# led_matrix_serial.net
KiCad netlist of a schematic drawn in Altium Designer
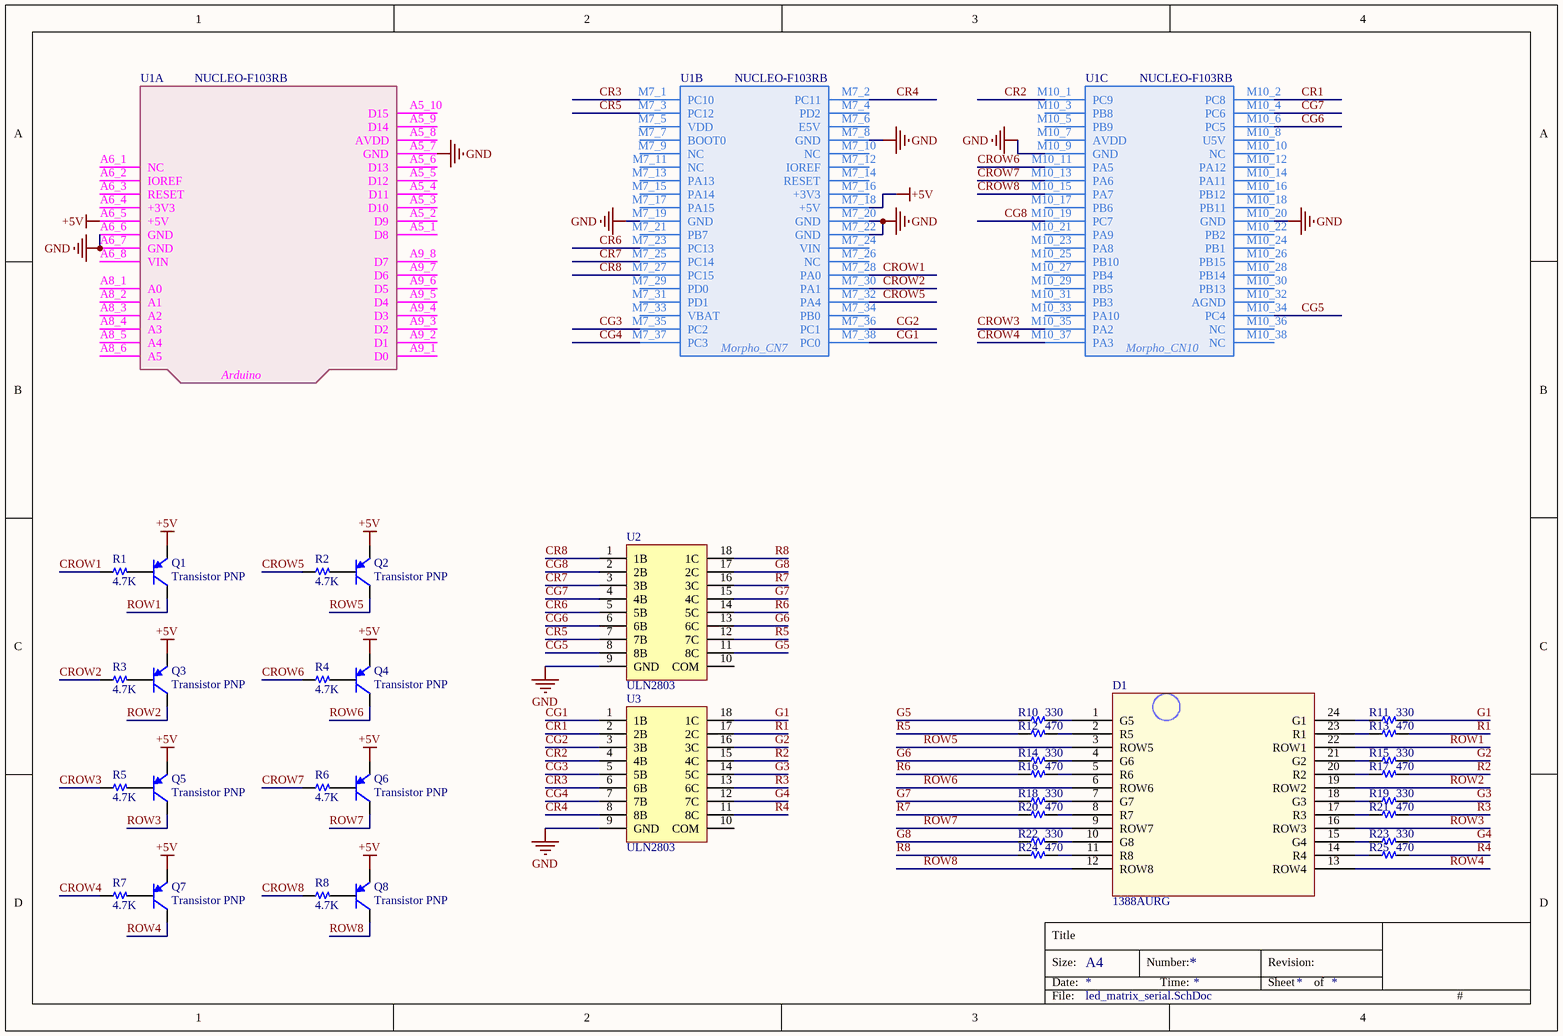
[diagram p0: led_matrix_serial.SchDoc]

(export (version "E")
  (design (tool "Eeschema 10.0.6"))
  (components
    (comp (ref "D1")
      (value "1388AURG")
      (footprint "LED/MATRIX/1388")
      (description "1388AURG, Common-Anode, LED Matrix 8x8, RED-GREEN, 32x32mm")
      (libsource (lib "chipfc_altium_libs") (part "LED MATRIX 1388AURG"))
    )
    (comp (ref "Q1")
      (value "Transistor PNP")
      (footprint "SOT-23")
      (description "PNP Bipolar Transistor")
      (libsource (lib "chipfc_altium_libs") (part "Transistor PNP"))
    )
    (comp (ref "Q2")
      (value "Transistor PNP")
      (footprint "SOT-23")
      (description "PNP Bipolar Transistor")
      (libsource (lib "chipfc_altium_libs") (part "Transistor PNP"))
    )
    (comp (ref "Q3")
      (value "Transistor PNP")
      (footprint "SOT-23")
      (description "PNP Bipolar Transistor")
      (libsource (lib "chipfc_altium_libs") (part "Transistor PNP"))
    )
    (comp (ref "Q4")
      (value "Transistor PNP")
      (footprint "SOT-23")
      (description "PNP Bipolar Transistor")
      (libsource (lib "chipfc_altium_libs") (part "Transistor PNP"))
    )
    (comp (ref "Q5")
      (value "Transistor PNP")
      (footprint "SOT-23")
      (description "PNP Bipolar Transistor")
      (libsource (lib "chipfc_altium_libs") (part "Transistor PNP"))
    )
    (comp (ref "Q6")
      (value "Transistor PNP")
      (footprint "SOT-23")
      (description "PNP Bipolar Transistor")
      (libsource (lib "chipfc_altium_libs") (part "Transistor PNP"))
    )
    (comp (ref "Q7")
      (value "Transistor PNP")
      (footprint "SOT-23")
      (description "PNP Bipolar Transistor")
      (libsource (lib "chipfc_altium_libs") (part "Transistor PNP"))
    )
    (comp (ref "Q8")
      (value "Transistor PNP")
      (footprint "SOT-23")
      (description "PNP Bipolar Transistor")
      (libsource (lib "chipfc_altium_libs") (part "Transistor PNP"))
    )
    (comp (ref "R1")
      (value "4.7K")
      (footprint "R 0805")
      (description "Resistor")
      (libsource (lib "chipfc_altium_libs") (part "Resistor"))
    )
    (comp (ref "R2")
      (value "4.7K")
      (footprint "R 0805")
      (description "Resistor")
      (libsource (lib "chipfc_altium_libs") (part "Resistor"))
    )
    (comp (ref "R3")
      (value "4.7K")
      (footprint "R 0805")
      (description "Resistor")
      (libsource (lib "chipfc_altium_libs") (part "Resistor"))
    )
    (comp (ref "R4")
      (value "4.7K")
      (footprint "R 0805")
      (description "Resistor")
      (libsource (lib "chipfc_altium_libs") (part "Resistor"))
    )
    (comp (ref "R5")
      (value "4.7K")
      (footprint "R 0805")
      (description "Resistor")
      (libsource (lib "chipfc_altium_libs") (part "Resistor"))
    )
    (comp (ref "R6")
      (value "4.7K")
      (footprint "R 0805")
      (description "Resistor")
      (libsource (lib "chipfc_altium_libs") (part "Resistor"))
    )
    (comp (ref "R7")
      (value "4.7K")
      (footprint "R 0805")
      (description "Resistor")
      (libsource (lib "chipfc_altium_libs") (part "Resistor"))
    )
    (comp (ref "R8")
      (value "4.7K")
      (footprint "R 0805")
      (description "Resistor")
      (libsource (lib "chipfc_altium_libs") (part "Resistor"))
    )
    (comp (ref "R10")
      (value "330")
      (footprint "R 0805")
      (description "Resistor")
      (libsource (lib "chipfc_altium_libs") (part "Resistor"))
    )
    (comp (ref "R11")
      (value "330")
      (footprint "R 0805")
      (description "Resistor")
      (libsource (lib "chipfc_altium_libs") (part "Resistor"))
    )
    (comp (ref "R12")
      (value "470")
      (footprint "R 0805")
      (description "Resistor")
      (libsource (lib "chipfc_altium_libs") (part "Resistor"))
    )
    (comp (ref "R13")
      (value "470")
      (footprint "R 0805")
      (description "Resistor")
      (libsource (lib "chipfc_altium_libs") (part "Resistor"))
    )
    (comp (ref "R14")
      (value "330")
      (footprint "R 0805")
      (description "Resistor")
      (libsource (lib "chipfc_altium_libs") (part "Resistor"))
    )
    (comp (ref "R15")
      (value "330")
      (footprint "R 0805")
      (description "Resistor")
      (libsource (lib "chipfc_altium_libs") (part "Resistor"))
    )
    (comp (ref "R16")
      (value "470")
      (footprint "R 0805")
      (description "Resistor")
      (libsource (lib "chipfc_altium_libs") (part "Resistor"))
    )
    (comp (ref "R17")
      (value "470")
      (footprint "R 0805")
      (description "Resistor")
      (libsource (lib "chipfc_altium_libs") (part "Resistor"))
    )
    (comp (ref "R18")
      (value "330")
      (footprint "R 0805")
      (description "Resistor")
      (libsource (lib "chipfc_altium_libs") (part "Resistor"))
    )
    (comp (ref "R19")
      (value "330")
      (footprint "R 0805")
      (description "Resistor")
      (libsource (lib "chipfc_altium_libs") (part "Resistor"))
    )
    (comp (ref "R20")
      (value "470")
      (footprint "R 0805")
      (description "Resistor")
      (libsource (lib "chipfc_altium_libs") (part "Resistor"))
    )
    (comp (ref "R21")
      (value "470")
      (footprint "R 0805")
      (description "Resistor")
      (libsource (lib "chipfc_altium_libs") (part "Resistor"))
    )
    (comp (ref "R22")
      (value "330")
      (footprint "R 0805")
      (description "Resistor")
      (libsource (lib "chipfc_altium_libs") (part "Resistor"))
    )
    (comp (ref "R23")
      (value "330")
      (footprint "R 0805")
      (description "Resistor")
      (libsource (lib "chipfc_altium_libs") (part "Resistor"))
    )
    (comp (ref "R24")
      (value "470")
      (footprint "R 0805")
      (description "Resistor")
      (libsource (lib "chipfc_altium_libs") (part "Resistor"))
    )
    (comp (ref "R25")
      (value "470")
      (footprint "R 0805")
      (description "Resistor")
      (libsource (lib "chipfc_altium_libs") (part "Resistor"))
    )
    (comp (ref "U1")
      (value "NUCLEO-F103RB")
      (footprint "NUCLEO")
      (fields (field (name "MANUFACTURER") "STMicroelectronics"))
      (libsource (lib "nucleo") (part "NUCLEO-F103RB"))
    )
    (comp (ref "U2")
      (value "ULN2803")
      (footprint "SOP 18 50p")
      (description "TRANS 8NPN DARL 50V 0.5A 18SO")
      (fields (field (name "PART NO") "ULN2803ADWR"))
      (libsource (lib "chipfc_altium_libs") (part "ULN2803"))
    )
    (comp (ref "U3")
      (value "ULN2803")
      (footprint "SOP 18 50p")
      (description "TRANS 8NPN DARL 50V 0.5A 18SO")
      (fields (field (name "PART NO") "ULN2803ADWR"))
      (libsource (lib "chipfc_altium_libs") (part "ULN2803"))
    )
  )
  (nets
    (net (code "1") (name "+5V") (class "Default")
      (node (ref "Q1") (pin "2") (pinfunction "E_2") (pintype "passive"))
      (node (ref "Q2") (pin "2") (pinfunction "E_2") (pintype "passive"))
      (node (ref "Q3") (pin "2") (pinfunction "E_2") (pintype "passive"))
      (node (ref "Q4") (pin "2") (pinfunction "E_2") (pintype "passive"))
      (node (ref "Q5") (pin "2") (pinfunction "E_2") (pintype "passive"))
      (node (ref "Q6") (pin "2") (pinfunction "E_2") (pintype "passive"))
      (node (ref "Q7") (pin "2") (pinfunction "E_2") (pintype "passive"))
      (node (ref "Q8") (pin "2") (pinfunction "E_2") (pintype "passive"))
      (node (ref "U1") (pin "A6_5") (pinfunction "+5V_A6_5") (pintype "passive"))
      (node (ref "U1") (pin "M7_18") (pinfunction "+5V_M7_18") (pintype "passive"))
    )
    (net (code "2") (name "/CG1") (class "Default")
      (node (ref "U1") (pin "M7_38") (pinfunction "PC0_M7_38") (pintype "passive"))
      (node (ref "U3") (pin "1") (pinfunction "1B_1") (pintype "passive"))
    )
    (net (code "3") (name "/CG2") (class "Default")
      (node (ref "U1") (pin "M7_36") (pinfunction "PC1_M7_36") (pintype "passive"))
      (node (ref "U3") (pin "3") (pinfunction "3B_3") (pintype "passive"))
    )
    (net (code "4") (name "/CG3") (class "Default")
      (node (ref "U1") (pin "M7_35") (pinfunction "PC2_M7_35") (pintype "passive"))
      (node (ref "U3") (pin "5") (pinfunction "5B_5") (pintype "passive"))
    )
    (net (code "5") (name "/CG4") (class "Default")
      (node (ref "U1") (pin "M7_37") (pinfunction "PC3_M7_37") (pintype "passive"))
      (node (ref "U3") (pin "7") (pinfunction "7B_7") (pintype "passive"))
    )
    (net (code "6") (name "/CG5") (class "Default")
      (node (ref "U1") (pin "M10_34") (pinfunction "PC4_M10_34") (pintype "passive"))
      (node (ref "U2") (pin "8") (pinfunction "8B_8") (pintype "passive"))
    )
    (net (code "7") (name "/CG6") (class "Default")
      (node (ref "U1") (pin "M10_6") (pinfunction "PC5_M10_6") (pintype "passive"))
      (node (ref "U2") (pin "6") (pinfunction "6B_6") (pintype "passive"))
    )
    (net (code "8") (name "/CG7") (class "Default")
      (node (ref "U1") (pin "M10_4") (pinfunction "PC6_M10_4") (pintype "passive"))
      (node (ref "U2") (pin "4") (pinfunction "4B_4") (pintype "passive"))
    )
    (net (code "9") (name "/CG8") (class "Default")
      (node (ref "U1") (pin "M10_19") (pinfunction "PC7_M10_19") (pintype "passive"))
      (node (ref "U2") (pin "2") (pinfunction "2B_2") (pintype "passive"))
    )
    (net (code "10") (name "/CR1") (class "Default")
      (node (ref "U1") (pin "M10_2") (pinfunction "PC8_M10_2") (pintype "passive"))
      (node (ref "U3") (pin "2") (pinfunction "2B_2") (pintype "passive"))
    )
    (net (code "11") (name "/CR2") (class "Default")
      (node (ref "U1") (pin "M10_1") (pinfunction "PC9_M10_1") (pintype "passive"))
      (node (ref "U3") (pin "4") (pinfunction "4B_4") (pintype "passive"))
    )
    (net (code "12") (name "/CR3") (class "Default")
      (node (ref "U1") (pin "M7_1") (pinfunction "PC10_M7_1") (pintype "passive"))
      (node (ref "U3") (pin "6") (pinfunction "6B_6") (pintype "passive"))
    )
    (net (code "13") (name "/CR4") (class "Default")
      (node (ref "U1") (pin "M7_2") (pinfunction "PC11_M7_2") (pintype "passive"))
      (node (ref "U3") (pin "8") (pinfunction "8B_8") (pintype "passive"))
    )
    (net (code "14") (name "/CR5") (class "Default")
      (node (ref "U1") (pin "M7_3") (pinfunction "PC12_M7_3") (pintype "passive"))
      (node (ref "U2") (pin "7") (pinfunction "7B_7") (pintype "passive"))
    )
    (net (code "15") (name "/CR6") (class "Default")
      (node (ref "U1") (pin "M7_23") (pinfunction "PC13_M7_23") (pintype "passive"))
      (node (ref "U2") (pin "5") (pinfunction "5B_5") (pintype "passive"))
    )
    (net (code "16") (name "/CR7") (class "Default")
      (node (ref "U1") (pin "M7_25") (pinfunction "PC14_M7_25") (pintype "passive"))
      (node (ref "U2") (pin "3") (pinfunction "3B_3") (pintype "passive"))
    )
    (net (code "17") (name "/CR8") (class "Default")
      (node (ref "U1") (pin "M7_27") (pinfunction "PC15_M7_27") (pintype "passive"))
      (node (ref "U2") (pin "1") (pinfunction "1B_1") (pintype "passive"))
    )
    (net (code "18") (name "/CROW1") (class "Default")
      (node (ref "R1") (pin "1") (pinfunction "1_1") (pintype "passive"))
      (node (ref "U1") (pin "M7_28") (pinfunction "PA0_M7_28") (pintype "passive"))
    )
    (net (code "19") (name "/CROW2") (class "Default")
      (node (ref "R3") (pin "1") (pinfunction "1_1") (pintype "passive"))
      (node (ref "U1") (pin "M7_30") (pinfunction "PA1_M7_30") (pintype "passive"))
    )
    (net (code "20") (name "/CROW3") (class "Default")
      (node (ref "R5") (pin "1") (pinfunction "1_1") (pintype "passive"))
      (node (ref "U1") (pin "M10_35") (pinfunction "PA2_M10_35") (pintype "passive"))
    )
    (net (code "21") (name "/CROW4") (class "Default")
      (node (ref "R7") (pin "1") (pinfunction "1_1") (pintype "passive"))
      (node (ref "U1") (pin "M10_37") (pinfunction "PA3_M10_37") (pintype "passive"))
    )
    (net (code "22") (name "/CROW5") (class "Default")
      (node (ref "R2") (pin "1") (pinfunction "1_1") (pintype "passive"))
      (node (ref "U1") (pin "M7_32") (pinfunction "PA4_M7_32") (pintype "passive"))
    )
    (net (code "23") (name "/CROW6") (class "Default")
      (node (ref "R4") (pin "1") (pinfunction "1_1") (pintype "passive"))
      (node (ref "U1") (pin "M10_11") (pinfunction "PA5_M10_11") (pintype "passive"))
    )
    (net (code "24") (name "/CROW7") (class "Default")
      (node (ref "R6") (pin "1") (pinfunction "1_1") (pintype "passive"))
      (node (ref "U1") (pin "M10_13") (pinfunction "PA6_M10_13") (pintype "passive"))
    )
    (net (code "25") (name "/CROW8") (class "Default")
      (node (ref "R8") (pin "1") (pinfunction "1_1") (pintype "passive"))
      (node (ref "U1") (pin "M10_15") (pinfunction "PA7_M10_15") (pintype "passive"))
    )
    (net (code "26") (name "/G1") (class "Default")
      (node (ref "R11") (pin "2") (pinfunction "2_2") (pintype "passive"))
      (node (ref "U3") (pin "18") (pinfunction "1C_18") (pintype "passive"))
    )
    (net (code "27") (name "/G2") (class "Default")
      (node (ref "R15") (pin "2") (pinfunction "2_2") (pintype "passive"))
      (node (ref "U3") (pin "16") (pinfunction "3C_16") (pintype "passive"))
    )
    (net (code "28") (name "/G3") (class "Default")
      (node (ref "R19") (pin "2") (pinfunction "2_2") (pintype "passive"))
      (node (ref "U3") (pin "14") (pinfunction "5C_14") (pintype "passive"))
    )
    (net (code "29") (name "/G4") (class "Default")
      (node (ref "R23") (pin "2") (pinfunction "2_2") (pintype "passive"))
      (node (ref "U3") (pin "12") (pinfunction "7C_12") (pintype "passive"))
    )
    (net (code "30") (name "/G5") (class "Default")
      (node (ref "R10") (pin "1") (pinfunction "1_1") (pintype "passive"))
      (node (ref "U2") (pin "11") (pinfunction "8C_11") (pintype "passive"))
    )
    (net (code "31") (name "/G6") (class "Default")
      (node (ref "R14") (pin "1") (pinfunction "1_1") (pintype "passive"))
      (node (ref "U2") (pin "13") (pinfunction "6C_13") (pintype "passive"))
    )
    (net (code "32") (name "/G7") (class "Default")
      (node (ref "R18") (pin "1") (pinfunction "1_1") (pintype "passive"))
      (node (ref "U2") (pin "15") (pinfunction "4C_15") (pintype "passive"))
    )
    (net (code "33") (name "/G8") (class "Default")
      (node (ref "R22") (pin "1") (pinfunction "1_1") (pintype "passive"))
      (node (ref "U2") (pin "17") (pinfunction "2C_17") (pintype "passive"))
    )
    (net (code "34") (name "/R1") (class "Default")
      (node (ref "R13") (pin "2") (pinfunction "2_2") (pintype "passive"))
      (node (ref "U3") (pin "17") (pinfunction "2C_17") (pintype "passive"))
    )
    (net (code "35") (name "/R2") (class "Default")
      (node (ref "R17") (pin "2") (pinfunction "2_2") (pintype "passive"))
      (node (ref "U3") (pin "15") (pinfunction "4C_15") (pintype "passive"))
    )
    (net (code "36") (name "/R3") (class "Default")
      (node (ref "R21") (pin "2") (pinfunction "2_2") (pintype "passive"))
      (node (ref "U3") (pin "13") (pinfunction "6C_13") (pintype "passive"))
    )
    (net (code "37") (name "/R4") (class "Default")
      (node (ref "R25") (pin "2") (pinfunction "2_2") (pintype "passive"))
      (node (ref "U3") (pin "11") (pinfunction "8C_11") (pintype "passive"))
    )
    (net (code "38") (name "/R5") (class "Default")
      (node (ref "R12") (pin "1") (pinfunction "1_1") (pintype "passive"))
      (node (ref "U2") (pin "12") (pinfunction "7C_12") (pintype "passive"))
    )
    (net (code "39") (name "/R6") (class "Default")
      (node (ref "R16") (pin "1") (pinfunction "1_1") (pintype "passive"))
      (node (ref "U2") (pin "14") (pinfunction "5C_14") (pintype "passive"))
    )
    (net (code "40") (name "/R7") (class "Default")
      (node (ref "R20") (pin "1") (pinfunction "1_1") (pintype "passive"))
      (node (ref "U2") (pin "16") (pinfunction "3C_16") (pintype "passive"))
    )
    (net (code "41") (name "/R8") (class "Default")
      (node (ref "R24") (pin "1") (pinfunction "1_1") (pintype "passive"))
      (node (ref "U2") (pin "18") (pinfunction "1C_18") (pintype "passive"))
    )
    (net (code "42") (name "/ROW1") (class "Default")
      (node (ref "D1") (pin "22") (pinfunction "ROW1_22") (pintype "passive"))
      (node (ref "Q1") (pin "3") (pinfunction "C_3") (pintype "passive"))
    )
    (net (code "43") (name "/ROW2") (class "Default")
      (node (ref "D1") (pin "19") (pinfunction "ROW2_19") (pintype "passive"))
      (node (ref "Q3") (pin "3") (pinfunction "C_3") (pintype "passive"))
    )
    (net (code "44") (name "/ROW3") (class "Default")
      (node (ref "D1") (pin "16") (pinfunction "ROW3_16") (pintype "passive"))
      (node (ref "Q5") (pin "3") (pinfunction "C_3") (pintype "passive"))
    )
    (net (code "45") (name "/ROW4") (class "Default")
      (node (ref "D1") (pin "13") (pinfunction "ROW4_13") (pintype "passive"))
      (node (ref "Q7") (pin "3") (pinfunction "C_3") (pintype "passive"))
    )
    (net (code "46") (name "/ROW5") (class "Default")
      (node (ref "D1") (pin "3") (pinfunction "ROW5_3") (pintype "passive"))
      (node (ref "Q2") (pin "3") (pinfunction "C_3") (pintype "passive"))
    )
    (net (code "47") (name "/ROW6") (class "Default")
      (node (ref "D1") (pin "6") (pinfunction "ROW6_6") (pintype "passive"))
      (node (ref "Q4") (pin "3") (pinfunction "C_3") (pintype "passive"))
    )
    (net (code "48") (name "/ROW7") (class "Default")
      (node (ref "D1") (pin "9") (pinfunction "ROW7_9") (pintype "passive"))
      (node (ref "Q6") (pin "3") (pinfunction "C_3") (pintype "passive"))
    )
    (net (code "49") (name "/ROW8") (class "Default")
      (node (ref "D1") (pin "12") (pinfunction "ROW8_12") (pintype "passive"))
      (node (ref "Q8") (pin "3") (pinfunction "C_3") (pintype "passive"))
    )
    (net (code "50") (name "GND") (class "Default")
      (node (ref "U1") (pin "A5_7") (pinfunction "GND_A5_7") (pintype "passive"))
      (node (ref "U1") (pin "A6_6") (pinfunction "GND_A6_6") (pintype "passive"))
      (node (ref "U1") (pin "A6_7") (pinfunction "GND_A6_7") (pintype "passive"))
      (node (ref "U1") (pin "M10_20") (pinfunction "GND_M10_20") (pintype "passive"))
      (node (ref "U1") (pin "M10_9") (pinfunction "GND_M10_9") (pintype "passive"))
      (node (ref "U1") (pin "M7_19") (pinfunction "GND_M7_19") (pintype "passive"))
      (node (ref "U1") (pin "M7_20") (pinfunction "GND_M7_20") (pintype "passive"))
      (node (ref "U1") (pin "M7_22") (pinfunction "GND_M7_22") (pintype "passive"))
      (node (ref "U1") (pin "M7_8") (pinfunction "GND_M7_8") (pintype "passive"))
      (node (ref "U2") (pin "9") (pinfunction "GND_9") (pintype "passive"))
      (node (ref "U3") (pin "9") (pinfunction "GND_9") (pintype "passive"))
    )
    (net (code "51") (name "Net-(D1-G1)") (class "Default")
      (node (ref "D1") (pin "24") (pinfunction "G1_24") (pintype "passive"))
      (node (ref "R11") (pin "1") (pinfunction "1_1") (pintype "passive"))
    )
    (net (code "52") (name "Net-(D1-G2)") (class "Default")
      (node (ref "D1") (pin "21") (pinfunction "G2_21") (pintype "passive"))
      (node (ref "R15") (pin "1") (pinfunction "1_1") (pintype "passive"))
    )
    (net (code "53") (name "Net-(D1-G3)") (class "Default")
      (node (ref "D1") (pin "18") (pinfunction "G3_18") (pintype "passive"))
      (node (ref "R19") (pin "1") (pinfunction "1_1") (pintype "passive"))
    )
    (net (code "54") (name "Net-(D1-G4)") (class "Default")
      (node (ref "D1") (pin "15") (pinfunction "G4_15") (pintype "passive"))
      (node (ref "R23") (pin "1") (pinfunction "1_1") (pintype "passive"))
    )
    (net (code "55") (name "Net-(D1-G5)") (class "Default")
      (node (ref "D1") (pin "1") (pinfunction "G5_1") (pintype "passive"))
      (node (ref "R10") (pin "2") (pinfunction "2_2") (pintype "passive"))
    )
    (net (code "56") (name "Net-(D1-G6)") (class "Default")
      (node (ref "D1") (pin "4") (pinfunction "G6_4") (pintype "passive"))
      (node (ref "R14") (pin "2") (pinfunction "2_2") (pintype "passive"))
    )
    (net (code "57") (name "Net-(D1-G7)") (class "Default")
      (node (ref "D1") (pin "7") (pinfunction "G7_7") (pintype "passive"))
      (node (ref "R18") (pin "2") (pinfunction "2_2") (pintype "passive"))
    )
    (net (code "58") (name "Net-(D1-G8)") (class "Default")
      (node (ref "D1") (pin "10") (pinfunction "G8_10") (pintype "passive"))
      (node (ref "R22") (pin "2") (pinfunction "2_2") (pintype "passive"))
    )
    (net (code "59") (name "Net-(D1-R1)") (class "Default")
      (node (ref "D1") (pin "23") (pinfunction "R1_23") (pintype "passive"))
      (node (ref "R13") (pin "1") (pinfunction "1_1") (pintype "passive"))
    )
    (net (code "60") (name "Net-(D1-R2)") (class "Default")
      (node (ref "D1") (pin "20") (pinfunction "R2_20") (pintype "passive"))
      (node (ref "R17") (pin "1") (pinfunction "1_1") (pintype "passive"))
    )
    (net (code "61") (name "Net-(D1-R3)") (class "Default")
      (node (ref "D1") (pin "17") (pinfunction "R3_17") (pintype "passive"))
      (node (ref "R21") (pin "1") (pinfunction "1_1") (pintype "passive"))
    )
    (net (code "62") (name "Net-(D1-R4)") (class "Default")
      (node (ref "D1") (pin "14") (pinfunction "R4_14") (pintype "passive"))
      (node (ref "R25") (pin "1") (pinfunction "1_1") (pintype "passive"))
    )
    (net (code "63") (name "Net-(D1-R5)") (class "Default")
      (node (ref "D1") (pin "2") (pinfunction "R5_2") (pintype "passive"))
      (node (ref "R12") (pin "2") (pinfunction "2_2") (pintype "passive"))
    )
    (net (code "64") (name "Net-(D1-R6)") (class "Default")
      (node (ref "D1") (pin "5") (pinfunction "R6_5") (pintype "passive"))
      (node (ref "R16") (pin "2") (pinfunction "2_2") (pintype "passive"))
    )
    (net (code "65") (name "Net-(D1-R7)") (class "Default")
      (node (ref "D1") (pin "8") (pinfunction "R7_8") (pintype "passive"))
      (node (ref "R20") (pin "2") (pinfunction "2_2") (pintype "passive"))
    )
    (net (code "66") (name "Net-(D1-R8)") (class "Default")
      (node (ref "D1") (pin "11") (pinfunction "R8_11") (pintype "passive"))
      (node (ref "R24") (pin "2") (pinfunction "2_2") (pintype "passive"))
    )
    (net (code "67") (name "Net-(Q1-B)") (class "Default")
      (node (ref "Q1") (pin "1") (pinfunction "B_1") (pintype "passive"))
      (node (ref "R1") (pin "2") (pinfunction "2_2") (pintype "passive"))
    )
    (net (code "68") (name "Net-(Q2-B)") (class "Default")
      (node (ref "Q2") (pin "1") (pinfunction "B_1") (pintype "passive"))
      (node (ref "R2") (pin "2") (pinfunction "2_2") (pintype "passive"))
    )
    (net (code "69") (name "Net-(Q3-B)") (class "Default")
      (node (ref "Q3") (pin "1") (pinfunction "B_1") (pintype "passive"))
      (node (ref "R3") (pin "2") (pinfunction "2_2") (pintype "passive"))
    )
    (net (code "70") (name "Net-(Q4-B)") (class "Default")
      (node (ref "Q4") (pin "1") (pinfunction "B_1") (pintype "passive"))
      (node (ref "R4") (pin "2") (pinfunction "2_2") (pintype "passive"))
    )
    (net (code "71") (name "Net-(Q5-B)") (class "Default")
      (node (ref "Q5") (pin "1") (pinfunction "B_1") (pintype "passive"))
      (node (ref "R5") (pin "2") (pinfunction "2_2") (pintype "passive"))
    )
    (net (code "72") (name "Net-(Q6-B)") (class "Default")
      (node (ref "Q6") (pin "1") (pinfunction "B_1") (pintype "passive"))
      (node (ref "R6") (pin "2") (pinfunction "2_2") (pintype "passive"))
    )
    (net (code "73") (name "Net-(Q7-B)") (class "Default")
      (node (ref "Q7") (pin "1") (pinfunction "B_1") (pintype "passive"))
      (node (ref "R7") (pin "2") (pinfunction "2_2") (pintype "passive"))
    )
    (net (code "74") (name "Net-(Q8-B)") (class "Default")
      (node (ref "Q8") (pin "1") (pinfunction "B_1") (pintype "passive"))
      (node (ref "R8") (pin "2") (pinfunction "2_2") (pintype "passive"))
    )
    (net (code "75") (name "unconnected-(U1A-+3V3-PadA6_4)") (class "Default")
      (node (ref "U1") (pin "A6_4") (pinfunction "+3V3_A6_4") (pintype "passive"))
    )
    (net (code "76") (name "unconnected-(U1A-A0-PadA8_1)") (class "Default")
      (node (ref "U1") (pin "A8_1") (pinfunction "A0_A8_1") (pintype "passive"))
    )
    (net (code "77") (name "unconnected-(U1A-A1-PadA8_2)") (class "Default")
      (node (ref "U1") (pin "A8_2") (pinfunction "A1_A8_2") (pintype "passive"))
    )
    (net (code "78") (name "unconnected-(U1A-A2-PadA8_3)") (class "Default")
      (node (ref "U1") (pin "A8_3") (pinfunction "A2_A8_3") (pintype "passive"))
    )
    (net (code "79") (name "unconnected-(U1A-A3-PadA8_4)") (class "Default")
      (node (ref "U1") (pin "A8_4") (pinfunction "A3_A8_4") (pintype "passive"))
    )
    (net (code "80") (name "unconnected-(U1A-A4-PadA8_5)") (class "Default")
      (node (ref "U1") (pin "A8_5") (pinfunction "A4_A8_5") (pintype "passive"))
    )
    (net (code "81") (name "unconnected-(U1A-A5-PadA8_6)") (class "Default")
      (node (ref "U1") (pin "A8_6") (pinfunction "A5_A8_6") (pintype "passive"))
    )
    (net (code "82") (name "unconnected-(U1A-AVDD-PadA5_8)") (class "Default")
      (node (ref "U1") (pin "A5_8") (pinfunction "AVDD_A5_8") (pintype "passive"))
    )
    (net (code "83") (name "unconnected-(U1A-D0-PadA9_1)") (class "Default")
      (node (ref "U1") (pin "A9_1") (pinfunction "D0_A9_1") (pintype "passive"))
    )
    (net (code "84") (name "unconnected-(U1A-D1-PadA9_2)") (class "Default")
      (node (ref "U1") (pin "A9_2") (pinfunction "D1_A9_2") (pintype "passive"))
    )
    (net (code "85") (name "unconnected-(U1A-D2-PadA9_3)") (class "Default")
      (node (ref "U1") (pin "A9_3") (pinfunction "D2_A9_3") (pintype "passive"))
    )
    (net (code "86") (name "unconnected-(U1A-D3-PadA9_4)") (class "Default")
      (node (ref "U1") (pin "A9_4") (pinfunction "D3_A9_4") (pintype "passive"))
    )
    (net (code "87") (name "unconnected-(U1A-D4-PadA9_5)") (class "Default")
      (node (ref "U1") (pin "A9_5") (pinfunction "D4_A9_5") (pintype "passive"))
    )
    (net (code "88") (name "unconnected-(U1A-D5-PadA9_6)") (class "Default")
      (node (ref "U1") (pin "A9_6") (pinfunction "D5_A9_6") (pintype "passive"))
    )
    (net (code "89") (name "unconnected-(U1A-D6-PadA9_7)") (class "Default")
      (node (ref "U1") (pin "A9_7") (pinfunction "D6_A9_7") (pintype "passive"))
    )
    (net (code "90") (name "unconnected-(U1A-D7-PadA9_8)") (class "Default")
      (node (ref "U1") (pin "A9_8") (pinfunction "D7_A9_8") (pintype "passive"))
    )
    (net (code "91") (name "unconnected-(U1A-D8-PadA5_1)") (class "Default")
      (node (ref "U1") (pin "A5_1") (pinfunction "D8_A5_1") (pintype "passive"))
    )
    (net (code "92") (name "unconnected-(U1A-D9-PadA5_2)") (class "Default")
      (node (ref "U1") (pin "A5_2") (pinfunction "D9_A5_2") (pintype "passive"))
    )
    (net (code "93") (name "unconnected-(U1A-D10-PadA5_3)") (class "Default")
      (node (ref "U1") (pin "A5_3") (pinfunction "D10_A5_3") (pintype "passive"))
    )
    (net (code "94") (name "unconnected-(U1A-D11-PadA5_4)") (class "Default")
      (node (ref "U1") (pin "A5_4") (pinfunction "D11_A5_4") (pintype "passive"))
    )
    (net (code "95") (name "unconnected-(U1A-D12-PadA5_5)") (class "Default")
      (node (ref "U1") (pin "A5_5") (pinfunction "D12_A5_5") (pintype "passive"))
    )
    (net (code "96") (name "unconnected-(U1A-D13-PadA5_6)") (class "Default")
      (node (ref "U1") (pin "A5_6") (pinfunction "D13_A5_6") (pintype "passive"))
    )
    (net (code "97") (name "unconnected-(U1A-D14-PadA5_9)") (class "Default")
      (node (ref "U1") (pin "A5_9") (pinfunction "D14_A5_9") (pintype "passive"))
    )
    (net (code "98") (name "unconnected-(U1A-D15-PadA5_10)") (class "Default")
      (node (ref "U1") (pin "A5_10") (pinfunction "D15_A5_10") (pintype "passive"))
    )
    (net (code "99") (name "unconnected-(U1A-IOREF-PadA6_2)") (class "Default")
      (node (ref "U1") (pin "A6_2") (pinfunction "IOREF_A6_2") (pintype "passive"))
    )
    (net (code "100") (name "unconnected-(U1A-NC-PadA6_1)") (class "Default")
      (node (ref "U1") (pin "A6_1") (pinfunction "NC_A6_1") (pintype "passive"))
    )
    (net (code "101") (name "unconnected-(U1A-RESET-PadA6_3)") (class "Default")
      (node (ref "U1") (pin "A6_3") (pinfunction "RESET_A6_3") (pintype "passive"))
    )
    (net (code "102") (name "unconnected-(U1A-VIN-PadA6_8)") (class "Default")
      (node (ref "U1") (pin "A6_8") (pinfunction "VIN_A6_8") (pintype "passive"))
    )
    (net (code "103") (name "unconnected-(U1B-+3V3-PadM7_16)") (class "Default")
      (node (ref "U1") (pin "M7_16") (pinfunction "+3V3_M7_16") (pintype "passive"))
    )
    (net (code "104") (name "unconnected-(U1B-BOOT0-PadM7_7)") (class "Default")
      (node (ref "U1") (pin "M7_7") (pinfunction "BOOT0_M7_7") (pintype "passive"))
    )
    (net (code "105") (name "unconnected-(U1B-E5V-PadM7_6)") (class "Default")
      (node (ref "U1") (pin "M7_6") (pinfunction "E5V_M7_6") (pintype "passive"))
    )
    (net (code "106") (name "unconnected-(U1B-IOREF-PadM7_12)") (class "Default")
      (node (ref "U1") (pin "M7_12") (pinfunction "IOREF_M7_12") (pintype "passive"))
    )
    (net (code "107") (name "unconnected-(U1B-NC-PadM7_9)") (class "Default")
      (node (ref "U1") (pin "M7_9") (pinfunction "NC_M7_9") (pintype "passive"))
    )
    (net (code "108") (name "unconnected-(U1B-NC-PadM7_10)") (class "Default")
      (node (ref "U1") (pin "M7_10") (pinfunction "NC_M7_10") (pintype "passive"))
    )
    (net (code "109") (name "unconnected-(U1B-NC-PadM7_11)") (class "Default")
      (node (ref "U1") (pin "M7_11") (pinfunction "NC_M7_11") (pintype "passive"))
    )
    (net (code "110") (name "unconnected-(U1B-NC-PadM7_26)") (class "Default")
      (node (ref "U1") (pin "M7_26") (pinfunction "NC_M7_26") (pintype "passive"))
    )
    (net (code "111") (name "unconnected-(U1B-PA13-PadM7_13)") (class "Default")
      (node (ref "U1") (pin "M7_13") (pinfunction "PA13_M7_13") (pintype "passive"))
    )
    (net (code "112") (name "unconnected-(U1B-PA14-PadM7_15)") (class "Default")
      (node (ref "U1") (pin "M7_15") (pinfunction "PA14_M7_15") (pintype "passive"))
    )
    (net (code "113") (name "unconnected-(U1B-PA15-PadM7_17)") (class "Default")
      (node (ref "U1") (pin "M7_17") (pinfunction "PA15_M7_17") (pintype "passive"))
    )
    (net (code "114") (name "unconnected-(U1B-PB0-PadM7_34)") (class "Default")
      (node (ref "U1") (pin "M7_34") (pinfunction "PB0_M7_34") (pintype "passive"))
    )
    (net (code "115") (name "unconnected-(U1B-PB7-PadM7_21)") (class "Default")
      (node (ref "U1") (pin "M7_21") (pinfunction "PB7_M7_21") (pintype "passive"))
    )
    (net (code "116") (name "unconnected-(U1B-PD0-PadM7_29)") (class "Default")
      (node (ref "U1") (pin "M7_29") (pinfunction "PD0_M7_29") (pintype "passive"))
    )
    (net (code "117") (name "unconnected-(U1B-PD1-PadM7_31)") (class "Default")
      (node (ref "U1") (pin "M7_31") (pinfunction "PD1_M7_31") (pintype "passive"))
    )
    (net (code "118") (name "unconnected-(U1B-PD2-PadM7_4)") (class "Default")
      (node (ref "U1") (pin "M7_4") (pinfunction "PD2_M7_4") (pintype "passive"))
    )
    (net (code "119") (name "unconnected-(U1B-RESET-PadM7_14)") (class "Default")
      (node (ref "U1") (pin "M7_14") (pinfunction "RESET_M7_14") (pintype "passive"))
    )
    (net (code "120") (name "unconnected-(U1B-VBAT-PadM7_33)") (class "Default")
      (node (ref "U1") (pin "M7_33") (pinfunction "VBAT_M7_33") (pintype "passive"))
    )
    (net (code "121") (name "unconnected-(U1B-VDD-PadM7_5)") (class "Default")
      (node (ref "U1") (pin "M7_5") (pinfunction "VDD_M7_5") (pintype "passive"))
    )
    (net (code "122") (name "unconnected-(U1B-VIN-PadM7_24)") (class "Default")
      (node (ref "U1") (pin "M7_24") (pinfunction "VIN_M7_24") (pintype "passive"))
    )
    (net (code "123") (name "unconnected-(U1C-AGND-PadM10_32)") (class "Default")
      (node (ref "U1") (pin "M10_32") (pinfunction "AGND_M10_32") (pintype "passive"))
    )
    (net (code "124") (name "unconnected-(U1C-AVDD-PadM10_7)") (class "Default")
      (node (ref "U1") (pin "M10_7") (pinfunction "AVDD_M10_7") (pintype "passive"))
    )
    (net (code "125") (name "unconnected-(U1C-NC-PadM10_10)") (class "Default")
      (node (ref "U1") (pin "M10_10") (pinfunction "NC_M10_10") (pintype "passive"))
    )
    (net (code "126") (name "unconnected-(U1C-NC-PadM10_36)") (class "Default")
      (node (ref "U1") (pin "M10_36") (pinfunction "NC_M10_36") (pintype "passive"))
    )
    (net (code "127") (name "unconnected-(U1C-NC-PadM10_38)") (class "Default")
      (node (ref "U1") (pin "M10_38") (pinfunction "NC_M10_38") (pintype "passive"))
    )
    (net (code "128") (name "unconnected-(U1C-PA8-PadM10_23)") (class "Default")
      (node (ref "U1") (pin "M10_23") (pinfunction "PA8_M10_23") (pintype "passive"))
    )
    (net (code "129") (name "unconnected-(U1C-PA9-PadM10_21)") (class "Default")
      (node (ref "U1") (pin "M10_21") (pinfunction "PA9_M10_21") (pintype "passive"))
    )
    (net (code "130") (name "unconnected-(U1C-PA10-PadM10_33)") (class "Default")
      (node (ref "U1") (pin "M10_33") (pinfunction "PA10_M10_33") (pintype "passive"))
    )
    (net (code "131") (name "unconnected-(U1C-PA11-PadM10_14)") (class "Default")
      (node (ref "U1") (pin "M10_14") (pinfunction "PA11_M10_14") (pintype "passive"))
    )
    (net (code "132") (name "unconnected-(U1C-PA12-PadM10_12)") (class "Default")
      (node (ref "U1") (pin "M10_12") (pinfunction "PA12_M10_12") (pintype "passive"))
    )
    (net (code "133") (name "unconnected-(U1C-PB1-PadM10_24)") (class "Default")
      (node (ref "U1") (pin "M10_24") (pinfunction "PB1_M10_24") (pintype "passive"))
    )
    (net (code "134") (name "unconnected-(U1C-PB2-PadM10_22)") (class "Default")
      (node (ref "U1") (pin "M10_22") (pinfunction "PB2_M10_22") (pintype "passive"))
    )
    (net (code "135") (name "unconnected-(U1C-PB3-PadM10_31)") (class "Default")
      (node (ref "U1") (pin "M10_31") (pinfunction "PB3_M10_31") (pintype "passive"))
    )
    (net (code "136") (name "unconnected-(U1C-PB4-PadM10_27)") (class "Default")
      (node (ref "U1") (pin "M10_27") (pinfunction "PB4_M10_27") (pintype "passive"))
    )
    (net (code "137") (name "unconnected-(U1C-PB5-PadM10_29)") (class "Default")
      (node (ref "U1") (pin "M10_29") (pinfunction "PB5_M10_29") (pintype "passive"))
    )
    (net (code "138") (name "unconnected-(U1C-PB6-PadM10_17)") (class "Default")
      (node (ref "U1") (pin "M10_17") (pinfunction "PB6_M10_17") (pintype "passive"))
    )
    (net (code "139") (name "unconnected-(U1C-PB8-PadM10_3)") (class "Default")
      (node (ref "U1") (pin "M10_3") (pinfunction "PB8_M10_3") (pintype "passive"))
    )
    (net (code "140") (name "unconnected-(U1C-PB9-PadM10_5)") (class "Default")
      (node (ref "U1") (pin "M10_5") (pinfunction "PB9_M10_5") (pintype "passive"))
    )
    (net (code "141") (name "unconnected-(U1C-PB10-PadM10_25)") (class "Default")
      (node (ref "U1") (pin "M10_25") (pinfunction "PB10_M10_25") (pintype "passive"))
    )
    (net (code "142") (name "unconnected-(U1C-PB11-PadM10_18)") (class "Default")
      (node (ref "U1") (pin "M10_18") (pinfunction "PB11_M10_18") (pintype "passive"))
    )
    (net (code "143") (name "unconnected-(U1C-PB12-PadM10_16)") (class "Default")
      (node (ref "U1") (pin "M10_16") (pinfunction "PB12_M10_16") (pintype "passive"))
    )
    (net (code "144") (name "unconnected-(U1C-PB13-PadM10_30)") (class "Default")
      (node (ref "U1") (pin "M10_30") (pinfunction "PB13_M10_30") (pintype "passive"))
    )
    (net (code "145") (name "unconnected-(U1C-PB14-PadM10_28)") (class "Default")
      (node (ref "U1") (pin "M10_28") (pinfunction "PB14_M10_28") (pintype "passive"))
    )
    (net (code "146") (name "unconnected-(U1C-PB15-PadM10_26)") (class "Default")
      (node (ref "U1") (pin "M10_26") (pinfunction "PB15_M10_26") (pintype "passive"))
    )
    (net (code "147") (name "unconnected-(U1C-U5V-PadM10_8)") (class "Default")
      (node (ref "U1") (pin "M10_8") (pinfunction "U5V_M10_8") (pintype "passive"))
    )
    (net (code "148") (name "unconnected-(U2-COM-Pad10)") (class "Default")
      (node (ref "U2") (pin "10") (pinfunction "COM_10") (pintype "passive"))
    )
    (net (code "149") (name "unconnected-(U3-COM-Pad10)") (class "Default")
      (node (ref "U3") (pin "10") (pinfunction "COM_10") (pintype "passive"))
    )
  )
)
